# STM32L0_PINOUT.net
KiCad netlist of a schematic drawn in Altium Designer
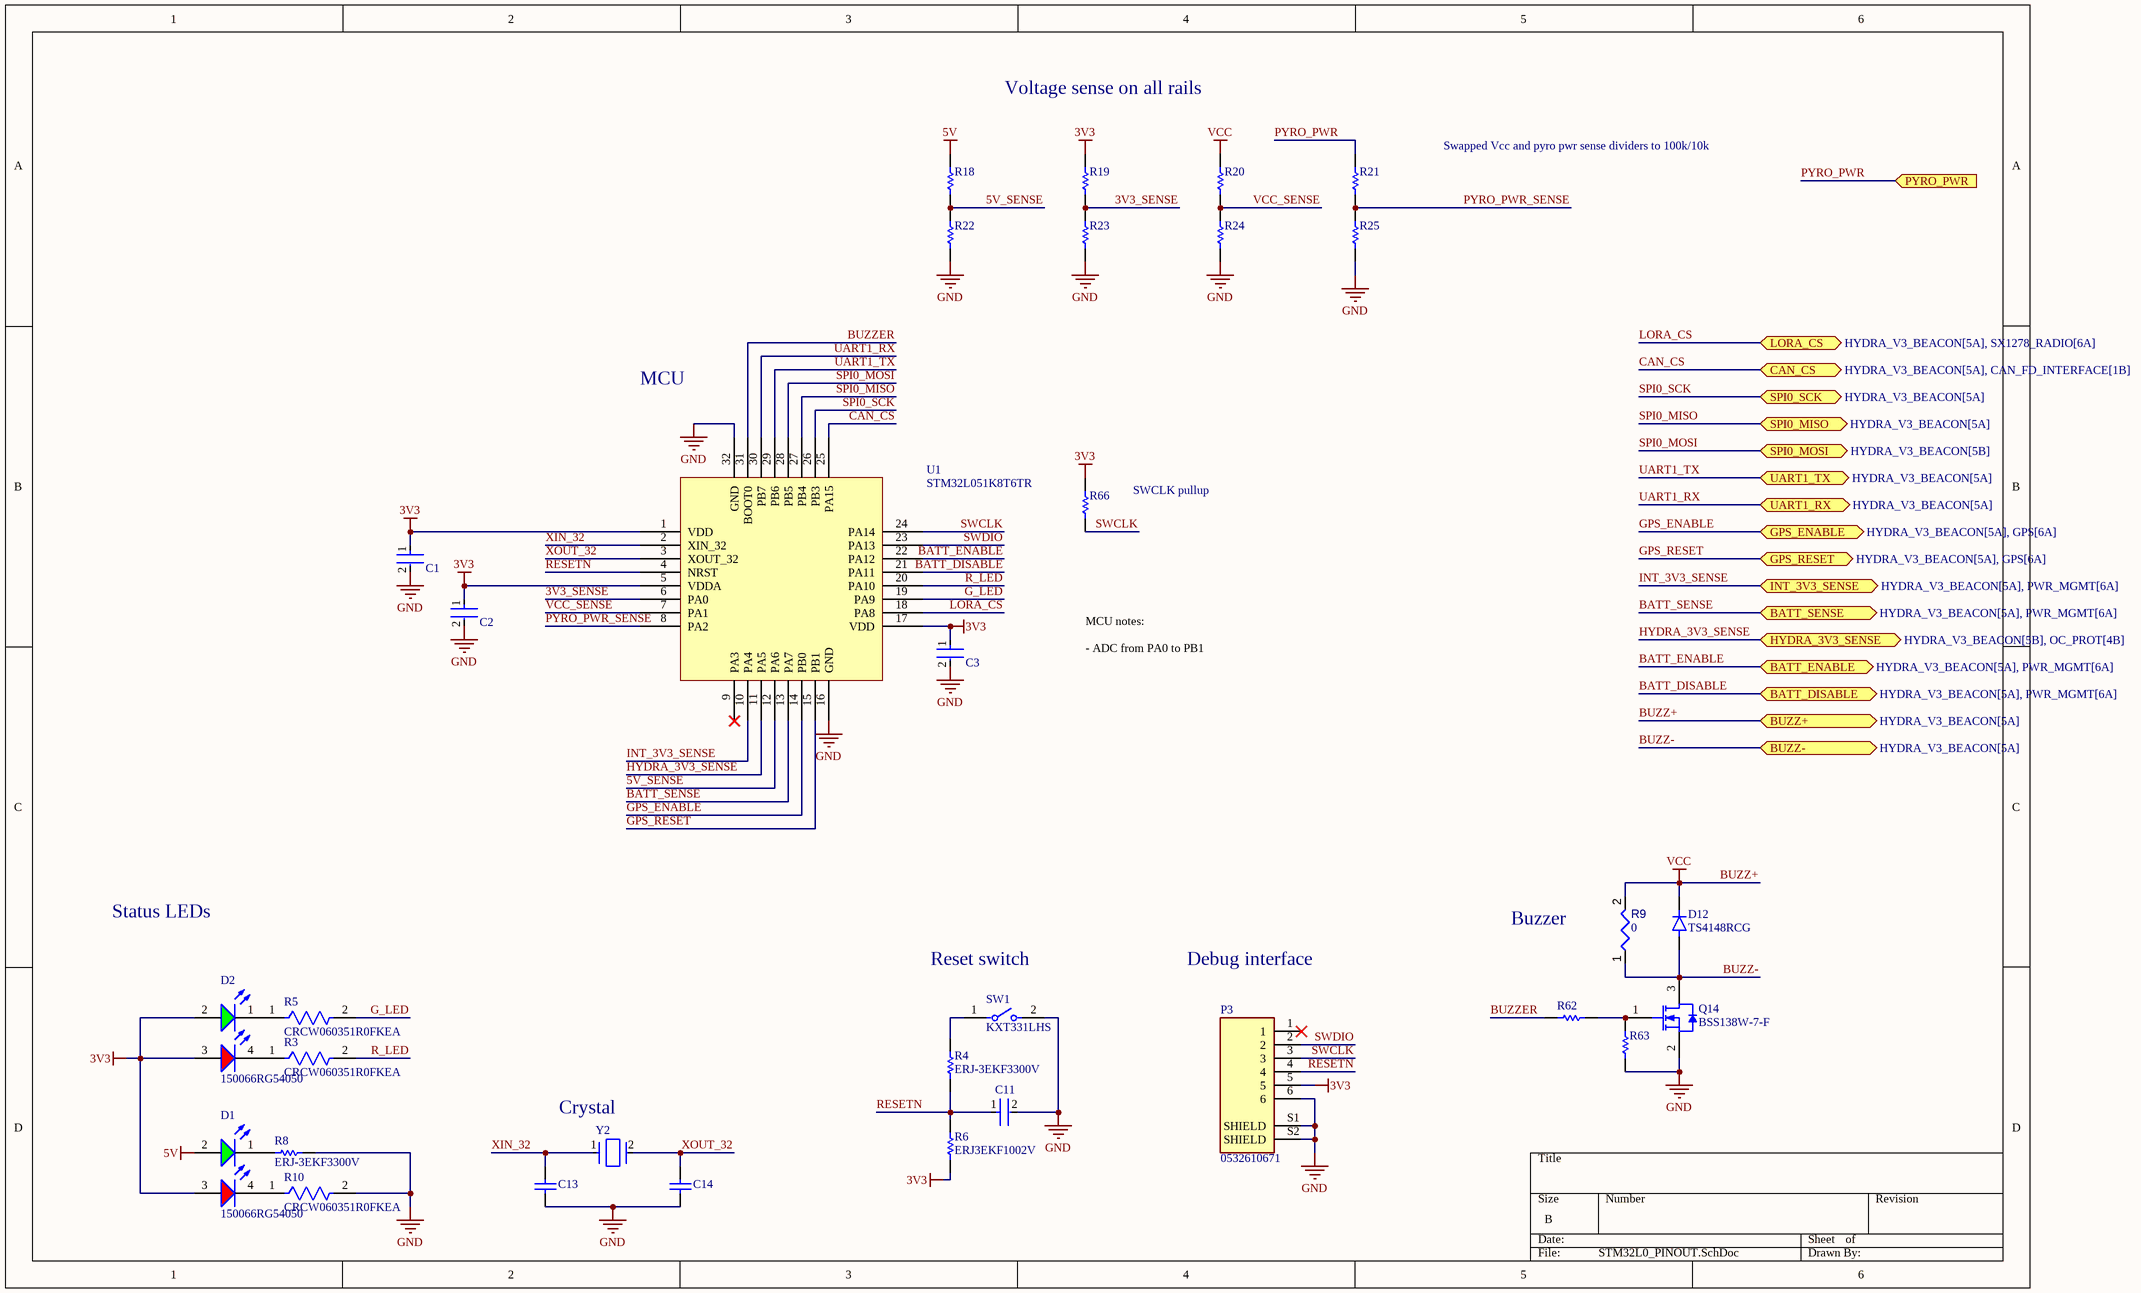
[diagram p0: STM32L0_PINOUT.SchDoc]

(export (version "E")
  (design (tool "Eeschema 10.0.6"))
  (components
    (comp (ref "C1")
      (value "C0402C104K8PACTU")
      (footprint "FP-C0402-BB-MFG")
      (description "CAP CER 0.1UF 10V X5R 0402")
      (fields (field (name "MANUFACTURER") "Kemet") (field (name "TOLERANCE") "0.1"))
      (libsource (lib "Altium Content Vault") (part "b4654b650e69147ec39a6b967a45e02"))
    )
    (comp (ref "C2")
      (value "C0402C104K8PACTU")
      (footprint "FP-C0402-BB-MFG")
      (description "CAP CER 0.1UF 10V X5R 0402")
      (fields (field (name "MANUFACTURER") "Kemet") (field (name "TOLERANCE") "0.1"))
      (libsource (lib "Altium Content Vault") (part "b4654b650e69147ec39a6b967a45e02"))
    )
    (comp (ref "C3")
      (value "C0402C104K8PACTU")
      (footprint "FP-C0402-BB-MFG")
      (description "CAP CER 0.1UF 10V X5R 0402")
      (fields (field (name "MANUFACTURER") "Kemet") (field (name "TOLERANCE") "0.1"))
      (libsource (lib "Altium Content Vault") (part "b4654b650e69147ec39a6b967a45e02"))
    )
    (comp (ref "C11")
      (value "C0402C104K8PACTU")
      (footprint "FP-C0402-BB-MFG")
      (description "CAP CER 0.1UF 10V X5R 0402")
      (fields (field (name "MANUFACTURER") "Kemet") (field (name "TOLERANCE") "0.1"))
      (libsource (lib "Altium Content Vault") (part "b4654b650e69147ec39a6b967a45e02"))
    )
    (comp (ref "C13")
      (value "CC0603JRNPO9BN180")
      (footprint "CAPC1608X90X40LL10T20")
      (description "Chip Capacitor, 18 pF, +/- 5%, 50 V, -55 to 125 degC, 0603 (1608 Metric), RoHS, Tape and Reel")
      (fields (field (name "TOLERANCE") "1%"))
      (libsource (lib "Altium Content Vault") (part "CAP-NP-2"))
    )
    (comp (ref "C14")
      (value "CC0603JRNPO9BN180")
      (footprint "CAPC1608X90X40LL10T20")
      (description "Chip Capacitor, 18 pF, +/- 5%, 50 V, -55 to 125 degC, 0603 (1608 Metric), RoHS, Tape and Reel")
      (fields (field (name "TOLERANCE") "1%"))
      (libsource (lib "Altium Content Vault") (part "CAP-NP-2"))
    )
    (comp (ref "D1")
      (value "150066RG54050")
      (footprint "WL-SBCD_0606")
      (description "Led, Red/Grn, 180Mcd/230Mcd, 624Nm/525Nm Rohs Compliant: Yes")
      (libsource (lib "uORocketry Hardware") (part "WL-SBCD_0606_Red & Green"))
    )
    (comp (ref "D2")
      (value "150066RG54050")
      (footprint "WL-SBCD_0606")
      (description "Led, Red/Grn, 180Mcd/230Mcd, 624Nm/525Nm Rohs Compliant: Yes")
      (libsource (lib "uORocketry Hardware") (part "WL-SBCD_0606_Red & Green"))
    )
    (comp (ref "D12")
      (value "TS4148RCG")
      (footprint "TS4148RCG-Footprint-1")
      (description "SMD Si-Diode 75V 100mA 0603")
      (libsource (lib "uORocketry Hardware") (part "TS4148RCG"))
    )
    (comp (ref "P3")
      (value "0532610671")
      (footprint "0532610671-Footprint-1")
      (description "Conn Shrouded Header (4 Sides) HDR 6 POS 1.25mm Solder RA Side Entry SMD PicoBlade™ T/R")
      (libsource (lib "uORocketry Hardware") (part "0532610671"))
    )
    (comp (ref "Q14")
      (value "BSS138W-7-F")
      (footprint "DIOD-SOT323-3_V")
      (fields (field (name "MANUFACTURER") "DiodesIncorporated"))
      (libsource (lib "Altium Content Vault") (part "NEMOS-GSD-3"))
    )
    (comp (ref "R3")
      (value "CRCW060351R0FKEA")
      (footprint "FP-CRCW0603-e3-MFG")
      (description "RES Thick Film, 51Ω, 1%, 0.1W, 100ppm/°C, 0603")
      (fields (field (name "TOLERANCE") "1%"))
      (libsource (lib "Altium Content Vault") (part "1029c3af85768c4190bb7ad29bc67b5"))
    )
    (comp (ref "R4")
      (value "ERJ-3EKF3300V")
      (footprint "RESC1608X55X30LL15T15")
      (description "Chip Resistor, 330 Ohm, +/- 1%, 0.1 W, -55 to 155 degC, 0603 (1608 Metric), RoHS, Tape and Reel")
      (libsource (lib "Altium Content Vault") (part "RES-2"))
    )
    (comp (ref "R5")
      (value "CRCW060351R0FKEA")
      (footprint "FP-CRCW0603-e3-MFG")
      (description "RES Thick Film, 51Ω, 1%, 0.1W, 100ppm/°C, 0603")
      (fields (field (name "TOLERANCE") "1%"))
      (libsource (lib "Altium Content Vault") (part "1029c3af85768c4190bb7ad29bc67b5"))
    )
    (comp (ref "R6")
      (value "ERJ3EKF1002V")
      (footprint "RESC1609X55X30LL15T15")
      (description "Chip Resistor, 10 KOhm, +/- 1%, 0.1 W, -55 to 155 degC, 0603 (1608 Metric), RoHS, Tape and Reel")
      (fields (field (name "TOLERANCE") "1%") (field (name "MANUFACTURER") "Panasonic"))
      (libsource (lib "Altium Content Vault") (part "RES-2"))
    )
    (comp (ref "R8")
      (value "ERJ-3EKF3300V")
      (footprint "RESC1608X55X30LL15T15")
      (description "Chip Resistor, 330 Ohm, +/- 1%, 0.1 W, -55 to 155 degC, 0603 (1608 Metric), RoHS, Tape and Reel")
      (libsource (lib "Altium Content Vault") (part "RES-2"))
    )
    (comp (ref "R9")
      (value "0")
      (footprint "RESC0603(1608)_L")
      (description "Jumper 0603 (1608 Metric)")
      (fields (field (name "Comment") "0R3J"))
      (libsource (lib "uORocketry Hardware") (part "0R3J"))
    )
    (comp (ref "R10")
      (value "CRCW060351R0FKEA")
      (footprint "FP-CRCW0603-e3-MFG")
      (description "RES Thick Film, 51Ω, 1%, 0.1W, 100ppm/°C, 0603")
      (fields (field (name "TOLERANCE") "1%"))
      (libsource (lib "Altium Content Vault") (part "1029c3af85768c4190bb7ad29bc67b5"))
    )
    (comp (ref "R18")
      (value "ERJ3EKF1002V")
      (footprint "RESC1609X55X30LL15T15")
      (description "Chip Resistor, 10 KOhm, +/- 1%, 0.1 W, -55 to 155 degC, 0603 (1608 Metric), RoHS, Tape and Reel")
      (fields (field (name "TOLERANCE") "1%") (field (name "MANUFACTURER") "Panasonic"))
      (libsource (lib "Altium Content Vault") (part "RES-2"))
    )
    (comp (ref "R19")
      (value "ERJ3EKF1002V")
      (footprint "RESC1609X55X30LL15T15")
      (description "Chip Resistor, 10 KOhm, +/- 1%, 0.1 W, -55 to 155 degC, 0603 (1608 Metric), RoHS, Tape and Reel")
      (fields (field (name "TOLERANCE") "1%") (field (name "MANUFACTURER") "Panasonic"))
      (libsource (lib "Altium Content Vault") (part "RES-2"))
    )
    (comp (ref "R20")
      (value "ERJ-3EKF1003V")
      (footprint "RESC1608X55X30ML15T15")
      (fields (field (name "MANUFACTURER") "Panasonic"))
      (libsource (lib "Altium Content Vault") (part "RES"))
    )
    (comp (ref "R21")
      (value "ERJ-3EKF1003V")
      (footprint "RESC1608X55X30ML15T15")
      (fields (field (name "MANUFACTURER") "Panasonic"))
      (libsource (lib "Altium Content Vault") (part "RES"))
    )
    (comp (ref "R22")
      (value "ERJ3EKF1002V")
      (footprint "RESC1609X55X30LL15T15")
      (description "Chip Resistor, 10 KOhm, +/- 1%, 0.1 W, -55 to 155 degC, 0603 (1608 Metric), RoHS, Tape and Reel")
      (fields (field (name "TOLERANCE") "1%") (field (name "MANUFACTURER") "Panasonic"))
      (libsource (lib "Altium Content Vault") (part "RES-2"))
    )
    (comp (ref "R23")
      (value "ERJ3EKF1002V")
      (footprint "RESC1609X55X30LL15T15")
      (description "Chip Resistor, 10 KOhm, +/- 1%, 0.1 W, -55 to 155 degC, 0603 (1608 Metric), RoHS, Tape and Reel")
      (fields (field (name "TOLERANCE") "1%") (field (name "MANUFACTURER") "Panasonic"))
      (libsource (lib "Altium Content Vault") (part "RES-2"))
    )
    (comp (ref "R24")
      (value "ERJ3EKF1002V")
      (footprint "RESC1609X55X30LL15T15")
      (description "Chip Resistor, 10 KOhm, +/- 1%, 0.1 W, -55 to 155 degC, 0603 (1608 Metric), RoHS, Tape and Reel")
      (fields (field (name "TOLERANCE") "1%") (field (name "MANUFACTURER") "Panasonic"))
      (libsource (lib "Altium Content Vault") (part "RES-2"))
    )
    (comp (ref "R25")
      (value "ERJ3EKF1002V")
      (footprint "RESC1609X55X30LL15T15")
      (description "Chip Resistor, 10 KOhm, +/- 1%, 0.1 W, -55 to 155 degC, 0603 (1608 Metric), RoHS, Tape and Reel")
      (fields (field (name "TOLERANCE") "1%") (field (name "MANUFACTURER") "Panasonic"))
      (libsource (lib "Altium Content Vault") (part "RES-2"))
    )
    (comp (ref "R62")
      (value "ERJ-3EKF1001V")
      (footprint "RESC1608X55X30LL15T15")
      (fields (field (name "MANUFACTURER") "Panasonic"))
      (libsource (lib "Altium Content Vault") (part "RES"))
    )
    (comp (ref "R63")
      (value "ERJ3EKF1002V")
      (footprint "RESC1609X55X30LL15T15")
      (description "Chip Resistor, 10 KOhm, +/- 1%, 0.1 W, -55 to 155 degC, 0603 (1608 Metric), RoHS, Tape and Reel")
      (fields (field (name "TOLERANCE") "1%") (field (name "MANUFACTURER") "Panasonic"))
      (libsource (lib "Altium Content Vault") (part "RES-2"))
    )
    (comp (ref "R66")
      (value "ERJ3EKF1002V")
      (footprint "RESC1609X55X30LL15T15")
      (description "Chip Resistor, 10 KOhm, +/- 1%, 0.1 W, -55 to 155 degC, 0603 (1608 Metric), RoHS, Tape and Reel")
      (fields (field (name "TOLERANCE") "1%") (field (name "MANUFACTURER") "Panasonic"))
      (libsource (lib "Altium Content Vault") (part "RES-2"))
    )
    (comp (ref "SW1")
      (value "KXT331LHS")
      (footprint "FP-KXT331LHS-MFG")
      (description "SWITCH TACTILE SPST-NO 0.02A 15V")
      (libsource (lib "Altium Content Vault") (part "bb27bde45df87f1f469753f287ef5ae"))
    )
    (comp (ref "U1")
      (value "STM32L051K8T6TR")
      (footprint "CQFP80P1115X1115X160-32N")
      (description "MCU 32-Bit Ultra Low Power STM32L ARM Cortex M0+ RISC 64kB Flash 32-Pin LQFP T/R")
      (libsource (lib "uORocketry Hardware") (part "STM32L051K8T6TR"))
    )
    (comp (ref "Y2")
      (value "ECS-.327-12.5-1210-TR")
      (footprint "FP-ECX-1210-MFG")
      (description "CRYSTAL 32.7680KHZ 12.5PF SMD")
      (fields
        (field (name "OCTOPART") "https://octopart.com/ecs-.327-12.5-1210-tr-ecs+international-81221340")
        (field (name "TOLERANCE") "20ppm")
      )
      (libsource (lib "Altium Content Vault") (part "99724985039315a44fd0d1401b84e49"))
    )
  )
  (nets
    (net (code "1") (name "/3V3_SENSE") (class "Default")
      (node (ref "R19") (pin "1") (pinfunction "1_1") (pintype "passive"))
      (node (ref "R23") (pin "2") (pinfunction "2_2") (pintype "passive"))
      (node (ref "U1") (pin "6") (pinfunction "PA0_6") (pintype "passive"))
    )
    (net (code "2") (name "/5V_SENSE") (class "Default")
      (node (ref "R18") (pin "1") (pinfunction "1_1") (pintype "passive"))
      (node (ref "R22") (pin "2") (pinfunction "2_2") (pintype "passive"))
      (node (ref "U1") (pin "12") (pinfunction "PA6_12") (pintype "passive"))
    )
    (net (code "3") (name "/BATT_DISABLE") (class "Default")
      (node (ref "U1") (pin "21") (pinfunction "PA11_21") (pintype "passive"))
    )
    (net (code "4") (name "/BATT_ENABLE") (class "Default")
      (node (ref "U1") (pin "22") (pinfunction "PA12_22") (pintype "passive"))
    )
    (net (code "5") (name "/BATT_SENSE") (class "Default")
      (node (ref "U1") (pin "13") (pinfunction "PA7_13") (pintype "passive"))
    )
    (net (code "6") (name "/BUZZ-") (class "Default")
      (node (ref "D12") (pin "A") (pinfunction "A_A") (pintype "passive"))
      (node (ref "Q14") (pin "3") (pinfunction "D_3") (pintype "passive"))
      (node (ref "R9") (pin "1") (pinfunction "1_1") (pintype "passive"))
    )
    (net (code "7") (name "/BUZZER") (class "Default")
      (node (ref "R62") (pin "2") (pinfunction "2_2") (pintype "passive"))
      (node (ref "U1") (pin "31") (pinfunction "BOOT0_31") (pintype "passive"))
    )
    (net (code "8") (name "/CAN_CS") (class "Default")
      (node (ref "U1") (pin "25") (pinfunction "PA15_25") (pintype "passive"))
    )
    (net (code "9") (name "/GPS_ENABLE") (class "Default")
      (node (ref "U1") (pin "14") (pinfunction "PB0_14") (pintype "passive"))
    )
    (net (code "10") (name "/GPS_RESET") (class "Default")
      (node (ref "U1") (pin "15") (pinfunction "PB1_15") (pintype "passive"))
    )
    (net (code "11") (name "/G_LED") (class "Default")
      (node (ref "R5") (pin "2") (pinfunction "2_2") (pintype "passive"))
      (node (ref "U1") (pin "19") (pinfunction "PA9_19") (pintype "passive"))
    )
    (net (code "12") (name "/HYDRA_3V3_SENSE") (class "Default")
      (node (ref "U1") (pin "11") (pinfunction "PA5_11") (pintype "passive"))
    )
    (net (code "13") (name "/INT_3V3_SENSE") (class "Default")
      (node (ref "U1") (pin "10") (pinfunction "PA4_10") (pintype "passive"))
    )
    (net (code "14") (name "/LORA_CS") (class "Default")
      (node (ref "U1") (pin "18") (pinfunction "PA8_18") (pintype "passive"))
    )
    (net (code "15") (name "/PYRO_PWR") (class "Default")
      (node (ref "R21") (pin "2") (pinfunction "2_2") (pintype "passive"))
    )
    (net (code "16") (name "/PYRO_PWR_SENSE") (class "Default")
      (node (ref "R21") (pin "1") (pinfunction "1_1") (pintype "passive"))
      (node (ref "R25") (pin "2") (pinfunction "2_2") (pintype "passive"))
      (node (ref "U1") (pin "8") (pinfunction "PA2_8") (pintype "passive"))
    )
    (net (code "17") (name "/RESETN") (class "Default")
      (node (ref "C11") (pin "1") (pinfunction "1_1") (pintype "passive"))
      (node (ref "P3") (pin "4") (pinfunction "4_4") (pintype "passive"))
      (node (ref "R4") (pin "1") (pinfunction "1_1") (pintype "passive"))
      (node (ref "R6") (pin "2") (pinfunction "2_2") (pintype "passive"))
      (node (ref "U1") (pin "4") (pinfunction "NRST_4") (pintype "passive"))
    )
    (net (code "18") (name "/R_LED") (class "Default")
      (node (ref "R3") (pin "2") (pinfunction "2_2") (pintype "passive"))
      (node (ref "U1") (pin "20") (pinfunction "PA10_20") (pintype "passive"))
    )
    (net (code "19") (name "/SPI0_MISO") (class "Default")
      (node (ref "U1") (pin "27") (pinfunction "PB4_27") (pintype "passive"))
    )
    (net (code "20") (name "/SPI0_MOSI") (class "Default")
      (node (ref "U1") (pin "28") (pinfunction "PB5_28") (pintype "passive"))
    )
    (net (code "21") (name "/SPI0_SCK") (class "Default")
      (node (ref "U1") (pin "26") (pinfunction "PB3_26") (pintype "passive"))
    )
    (net (code "22") (name "/SWCLK") (class "Default")
      (node (ref "P3") (pin "3") (pinfunction "3_3") (pintype "passive"))
      (node (ref "R66") (pin "1") (pinfunction "1_1") (pintype "passive"))
      (node (ref "U1") (pin "24") (pinfunction "PA14_24") (pintype "passive"))
    )
    (net (code "23") (name "/SWDIO") (class "Default")
      (node (ref "P3") (pin "2") (pinfunction "2_2") (pintype "passive"))
      (node (ref "U1") (pin "23") (pinfunction "PA13_23") (pintype "passive"))
    )
    (net (code "24") (name "/UART1_RX") (class "Default")
      (node (ref "U1") (pin "30") (pinfunction "PB7_30") (pintype "passive"))
    )
    (net (code "25") (name "/UART1_TX") (class "Default")
      (node (ref "U1") (pin "29") (pinfunction "PB6_29") (pintype "passive"))
    )
    (net (code "26") (name "/VCC_SENSE") (class "Default")
      (node (ref "R20") (pin "1") (pinfunction "1_1") (pintype "passive"))
      (node (ref "R24") (pin "2") (pinfunction "2_2") (pintype "passive"))
      (node (ref "U1") (pin "7") (pinfunction "PA1_7") (pintype "passive"))
    )
    (net (code "27") (name "/XIN_32") (class "Default")
      (node (ref "C13") (pin "2") (pinfunction "2_2") (pintype "passive"))
      (node (ref "U1") (pin "2") (pinfunction "XIN_32_2") (pintype "passive"))
      (node (ref "Y2") (pin "1") (pinfunction "In/Out_1") (pintype "passive"))
    )
    (net (code "28") (name "/XOUT_32") (class "Default")
      (node (ref "C14") (pin "2") (pinfunction "2_2") (pintype "passive"))
      (node (ref "U1") (pin "3") (pinfunction "XOUT_32_3") (pintype "passive"))
      (node (ref "Y2") (pin "2") (pinfunction "Out/In_2") (pintype "passive"))
    )
    (net (code "29") (name "3V3") (class "Default")
      (node (ref "C1") (pin "1") (pinfunction "1_1") (pintype "passive"))
      (node (ref "C2") (pin "1") (pinfunction "1_1") (pintype "passive"))
      (node (ref "C3") (pin "1") (pinfunction "1_1") (pintype "passive"))
      (node (ref "D1") (pin "3") (pinfunction "A_3") (pintype "passive"))
      (node (ref "D2") (pin "2") (pinfunction "A_2") (pintype "passive"))
      (node (ref "D2") (pin "3") (pinfunction "A_3") (pintype "passive"))
      (node (ref "P3") (pin "5") (pinfunction "5_5") (pintype "passive"))
      (node (ref "R19") (pin "2") (pinfunction "2_2") (pintype "passive"))
      (node (ref "R6") (pin "1") (pinfunction "1_1") (pintype "passive"))
      (node (ref "R66") (pin "2") (pinfunction "2_2") (pintype "passive"))
      (node (ref "U1") (pin "1") (pinfunction "VDD_1") (pintype "passive"))
      (node (ref "U1") (pin "17") (pinfunction "VDD_17") (pintype "passive"))
      (node (ref "U1") (pin "5") (pinfunction "VDDA_5") (pintype "passive"))
    )
    (net (code "30") (name "5V") (class "Default")
      (node (ref "D1") (pin "2") (pinfunction "A_2") (pintype "passive"))
      (node (ref "R18") (pin "2") (pinfunction "2_2") (pintype "passive"))
    )
    (net (code "31") (name "GND") (class "Default")
      (node (ref "C1") (pin "2") (pinfunction "2_2") (pintype "passive"))
      (node (ref "C11") (pin "2") (pinfunction "2_2") (pintype "passive"))
      (node (ref "C13") (pin "1") (pinfunction "1_1") (pintype "passive"))
      (node (ref "C14") (pin "1") (pinfunction "1_1") (pintype "passive"))
      (node (ref "C2") (pin "2") (pinfunction "2_2") (pintype "passive"))
      (node (ref "C3") (pin "2") (pinfunction "2_2") (pintype "passive"))
      (node (ref "P3") (pin "6") (pinfunction "6_6") (pintype "passive"))
      (node (ref "P3") (pin "S1") (pinfunction "SHIELD_S1") (pintype "passive"))
      (node (ref "P3") (pin "S2") (pinfunction "SHIELD_S2") (pintype "passive"))
      (node (ref "Q14") (pin "2") (pinfunction "S_2") (pintype "passive"))
      (node (ref "R10") (pin "2") (pinfunction "2_2") (pintype "passive"))
      (node (ref "R22") (pin "1") (pinfunction "1_1") (pintype "passive"))
      (node (ref "R23") (pin "1") (pinfunction "1_1") (pintype "passive"))
      (node (ref "R24") (pin "1") (pinfunction "1_1") (pintype "passive"))
      (node (ref "R25") (pin "1") (pinfunction "1_1") (pintype "passive"))
      (node (ref "R63") (pin "2") (pinfunction "2_2") (pintype "passive"))
      (node (ref "R8") (pin "2") (pinfunction "2_2") (pintype "passive"))
      (node (ref "SW1") (pin "2") (pinfunction "2_2") (pintype "passive"))
      (node (ref "U1") (pin "16") (pinfunction "GND_16") (pintype "passive"))
      (node (ref "U1") (pin "32") (pinfunction "GND_32") (pintype "passive"))
    )
    (net (code "32") (name "Net-(D1-K-Pad1)") (class "Default")
      (node (ref "D1") (pin "1") (pinfunction "K_1") (pintype "passive"))
      (node (ref "R8") (pin "1") (pinfunction "1_1") (pintype "passive"))
    )
    (net (code "33") (name "Net-(D1-K-Pad4)") (class "Default")
      (node (ref "D1") (pin "4") (pinfunction "K_4") (pintype "passive"))
      (node (ref "R10") (pin "1") (pinfunction "1_1") (pintype "passive"))
    )
    (net (code "34") (name "Net-(D2-K-Pad1)") (class "Default")
      (node (ref "D2") (pin "1") (pinfunction "K_1") (pintype "passive"))
      (node (ref "R5") (pin "1") (pinfunction "1_1") (pintype "passive"))
    )
    (net (code "35") (name "Net-(D2-K-Pad4)") (class "Default")
      (node (ref "D2") (pin "4") (pinfunction "K_4") (pintype "passive"))
      (node (ref "R3") (pin "1") (pinfunction "1_1") (pintype "passive"))
    )
    (net (code "36") (name "Net-(Q14-G)") (class "Default")
      (node (ref "Q14") (pin "1") (pinfunction "G_1") (pintype "passive"))
      (node (ref "R62") (pin "1") (pinfunction "1_1") (pintype "passive"))
      (node (ref "R63") (pin "1") (pinfunction "1_1") (pintype "passive"))
    )
    (net (code "37") (name "Net-(R4-Pad2)") (class "Default")
      (node (ref "R4") (pin "2") (pinfunction "2_2") (pintype "passive"))
      (node (ref "SW1") (pin "1") (pinfunction "1_1") (pintype "passive"))
    )
    (net (code "38") (name "VCC") (class "Default")
      (node (ref "D12") (pin "C") (pinfunction "K_C") (pintype "passive"))
      (node (ref "R20") (pin "2") (pinfunction "2_2") (pintype "passive"))
      (node (ref "R9") (pin "2") (pinfunction "2_2") (pintype "passive"))
    )
    (net (code "39") (name "unconnected-(P3-Pad1)") (class "Default")
      (node (ref "P3") (pin "1") (pinfunction "1_1") (pintype "passive+no_connect"))
    )
    (net (code "40") (name "unconnected-(U1-PA3-Pad9)") (class "Default")
      (node (ref "U1") (pin "9") (pinfunction "PA3_9") (pintype "passive+no_connect"))
    )
  )
)
